# PCR-Badge-2015.net
KiCad netlist of a schematic drawn in EAGLE
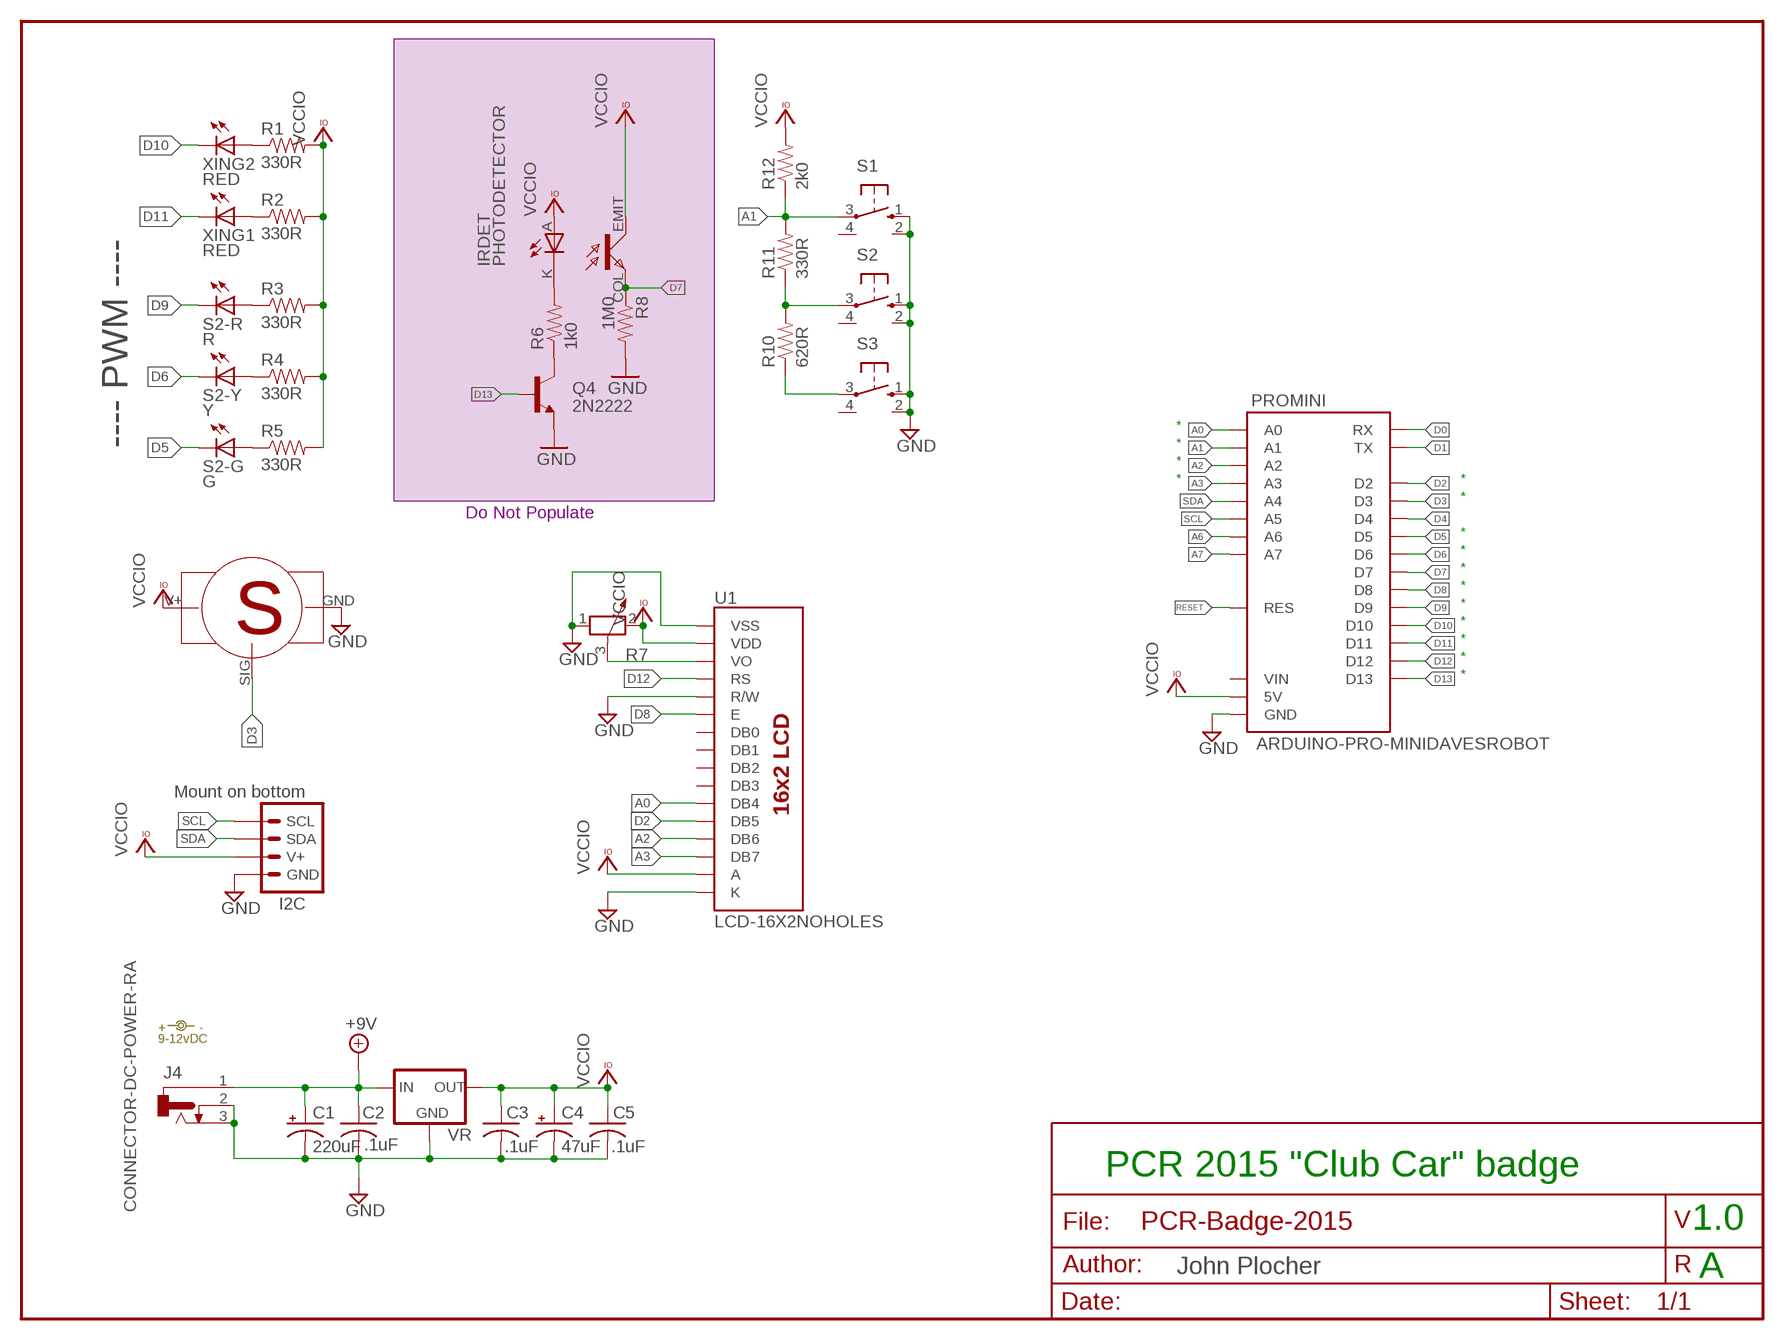
[diagram p0: schematic, sheet 1]

(export (version "E")
  (design (tool "Eeschema 10.0.6"))
  (components
    (comp (ref "C1")
      (value "220uF")
      (footprint "eagle-import:E5-10.5")
      (libsource (lib "eagle-import") (part "CAP-POLPTH-5MM"))
    )
    (comp (ref "C2")
      (value ".1uF")
      (footprint "eagle-import:C050-024X044")
      (libsource (lib "eagle-import") (part "CAP"))
    )
    (comp (ref "C3")
      (value ".1uF")
      (footprint "eagle-import:C050-024X044")
      (libsource (lib "eagle-import") (part "CAP"))
    )
    (comp (ref "C4")
      (value "47uF")
      (footprint "eagle-import:E5-10.5")
      (libsource (lib "eagle-import") (part "CAP-POLPTH-5MM"))
    )
    (comp (ref "C5")
      (value ".1uF")
      (footprint "eagle-import:C050-024X044")
      (libsource (lib "eagle-import") (part "CAP"))
    )
    (comp (ref "I2C")
      (value "Mount on bottom")
      (footprint "eagle-import:I2C")
      (libsource (lib "eagle-import") (part "CONNECTOR-I2C"))
    )
    (comp (ref "IRDET")
      (value "PHOTODETECTOR")
      (footprint "eagle-import:RPR220")
      (libsource (lib "eagle-import") (part "PHOTODETECTOR"))
    )
    (comp (ref "J4")
      (value "CONNECTOR-DC-POWER-RA")
      (footprint "eagle-import:DCJ0202")
      (libsource (lib "eagle-import") (part "CONNECTOR-DC-POWER-RA"))
    )
    (comp (ref "POWER")
      (value "9-12vDC")
      (footprint "eagle-import:POWER_USAGE")
      (libsource (lib "eagle-import") (part "DOC-POWER_LABEL"))
    )
    (comp (ref "PROMINI")
      (value "ARDUINO-PRO-MINIDAVESROBOT")
      (footprint "eagle-import:ARDUINO_PRO_MINI_DAVEK")
      (libsource (lib "eagle-import") (part "ARDUINO-PRO-MINIDAVESROBOT"))
    )
    (comp (ref "Q4")
      (value "2N2222")
      (footprint "eagle-import:TO-92")
      (libsource (lib "eagle-import") (part "NPN-TO92"))
    )
    (comp (ref "R1")
      (value "330R")
      (footprint "eagle-import:1_6W-RES")
      (libsource (lib "eagle-import") (part "RPTH-1/6W"))
    )
    (comp (ref "R2")
      (value "330R")
      (footprint "eagle-import:1_6W-RES")
      (libsource (lib "eagle-import") (part "RPTH-1/6W"))
    )
    (comp (ref "R3")
      (value "330R")
      (footprint "eagle-import:1_6W-RES")
      (libsource (lib "eagle-import") (part "RPTH-1/6W"))
    )
    (comp (ref "R4")
      (value "330R")
      (footprint "eagle-import:1_6W-RES")
      (libsource (lib "eagle-import") (part "RPTH-1/6W"))
    )
    (comp (ref "R5")
      (value "330R")
      (footprint "eagle-import:1_6W-RES")
      (libsource (lib "eagle-import") (part "RPTH-1/6W"))
    )
    (comp (ref "R6")
      (value "1k0")
      (footprint "eagle-import:1_6W-RES")
      (libsource (lib "eagle-import") (part "RPTH-1/6W"))
    )
    (comp (ref "R7")
      (value "R-POTENTIOMETERB25U")
      (footprint "eagle-import:B25U")
      (libsource (lib "eagle-import") (part "R-POTENTIOMETERB25U"))
    )
    (comp (ref "R8")
      (value "1M0")
      (footprint "eagle-import:1_6W-RES")
      (libsource (lib "eagle-import") (part "RPTH-1/6W"))
    )
    (comp (ref "R10")
      (value "620R")
      (footprint "eagle-import:1_6W-RES")
      (libsource (lib "eagle-import") (part "RPTH-1/6W"))
    )
    (comp (ref "R11")
      (value "330R")
      (footprint "eagle-import:1_6W-RES")
      (libsource (lib "eagle-import") (part "RPTH-1/6W"))
    )
    (comp (ref "R12")
      (value "2k0")
      (footprint "eagle-import:1_6W-RES")
      (libsource (lib "eagle-import") (part "RPTH-1/6W"))
    )
    (comp (ref "S1")
      (value "SWITCH-(ON)SMALLPADS")
      (footprint "eagle-import:4P-PTH-6.0X6.0X5.0H")
      (libsource (lib "eagle-import") (part "SWITCH-(ON)SMALLPADS"))
    )
    (comp (ref "S2")
      (value "SWITCH-(ON)SMALLPADS")
      (footprint "eagle-import:4P-PTH-6.0X6.0X5.0H")
      (libsource (lib "eagle-import") (part "SWITCH-(ON)SMALLPADS"))
    )
    (comp (ref "S2-G")
      (value "G")
      (footprint "eagle-import:LED5MM")
      (libsource (lib "eagle-import") (part "LEDLED5MM"))
    )
    (comp (ref "S2-R")
      (value "R")
      (footprint "eagle-import:LED5MM")
      (libsource (lib "eagle-import") (part "LEDLED5MM"))
    )
    (comp (ref "S2-Y")
      (value "Y")
      (footprint "eagle-import:LED5MM")
      (libsource (lib "eagle-import") (part "LEDLED5MM"))
    )
    (comp (ref "S3")
      (value "SWITCH-(ON)SMALLPADS")
      (footprint "eagle-import:4P-PTH-6.0X6.0X5.0H")
      (libsource (lib "eagle-import") (part "SWITCH-(ON)SMALLPADS"))
    )
    (comp (ref "SERVO")
      (value "SERVO")
      (footprint "eagle-import:SERVO")
      (libsource (lib "eagle-import") (part "SERVO"))
    )
    (comp (ref "SERVO1")
      (value "SERVO")
      (footprint "eagle-import:SERVO-9G")
      (libsource (lib "eagle-import") (part "SERVO-CUTOUT"))
    )
    (comp (ref "U1")
      (value "LCD-16X2NOHOLES")
      (footprint "eagle-import:LCD-16X2_NOHOLES")
      (libsource (lib "eagle-import") (part "LCD-16X2NOHOLES"))
    )
    (comp (ref "VR")
      (value "VREG_78XX-TO-220")
      (footprint "eagle-import:TO-220-ALT")
      (libsource (lib "eagle-import") (part "VREG_78XX-TO-220"))
    )
    (comp (ref "XING1")
      (value "RED")
      (footprint "eagle-import:LED5MM")
      (libsource (lib "eagle-import") (part "LEDLED5MM"))
    )
    (comp (ref "XING2")
      (value "RED")
      (footprint "eagle-import:LED5MM")
      (libsource (lib "eagle-import") (part "LEDLED5MM"))
    )
  )
  (nets
    (net (code "1") (name "+9V") (class "Default")
      (node (ref "C1") (pin "+") (pinfunction "+_+") (pintype "passive"))
      (node (ref "C2") (pin "1") (pinfunction "1_1") (pintype "passive"))
      (node (ref "J4") (pin "1") (pinfunction "1_1") (pintype "passive"))
      (node (ref "VR") (pin "IN") (pinfunction "IN_IN") (pintype "input"))
    )
    (net (code "2") (name "A0") (class "Default")
      (node (ref "PROMINI") (pin "AD0") (pinfunction "A0_AD0") (pintype "bidirectional"))
      (node (ref "U1") (pin "11") (pinfunction "DB4_11") (pintype "bidirectional"))
    )
    (net (code "3") (name "A1") (class "Default")
      (node (ref "PROMINI") (pin "AD1") (pinfunction "A1_AD1") (pintype "bidirectional"))
      (node (ref "R11") (pin "2") (pinfunction "2_2") (pintype "passive"))
      (node (ref "R12") (pin "1") (pinfunction "1_1") (pintype "passive"))
      (node (ref "S1") (pin "3") (pinfunction "P_3") (pintype "passive"))
    )
    (net (code "4") (name "A2") (class "Default")
      (node (ref "PROMINI") (pin "AD2") (pinfunction "A2_AD2") (pintype "bidirectional"))
      (node (ref "U1") (pin "13") (pinfunction "DB6_13") (pintype "bidirectional"))
    )
    (net (code "5") (name "A3") (class "Default")
      (node (ref "PROMINI") (pin "AD3") (pinfunction "A3_AD3") (pintype "bidirectional"))
      (node (ref "U1") (pin "14") (pinfunction "DB7_14") (pintype "bidirectional"))
    )
    (net (code "6") (name "A6") (class "Default")
      (node (ref "PROMINI") (pin "AD6") (pinfunction "A6_AD6") (pintype "bidirectional"))
    )
    (net (code "7") (name "A7") (class "Default")
      (node (ref "PROMINI") (pin "AD7") (pinfunction "A7_AD7") (pintype "bidirectional"))
    )
    (net (code "8") (name "D0") (class "Default")
      (node (ref "PROMINI") (pin "RX") (pinfunction "RX_RX") (pintype "bidirectional"))
    )
    (net (code "9") (name "D1") (class "Default")
      (node (ref "PROMINI") (pin "TX@1") (pinfunction "TX_TX@1") (pintype "bidirectional"))
    )
    (net (code "10") (name "D2") (class "Default")
      (node (ref "PROMINI") (pin "D2") (pinfunction "D2_D2") (pintype "bidirectional"))
      (node (ref "U1") (pin "12") (pinfunction "DB5_12") (pintype "bidirectional"))
    )
    (net (code "11") (name "D3") (class "Default")
      (node (ref "PROMINI") (pin "D3") (pinfunction "D3_D3") (pintype "bidirectional"))
      (node (ref "SERVO") (pin "SIG") (pinfunction "PWM_SIG") (pintype "input"))
    )
    (net (code "12") (name "D4") (class "Default")
      (node (ref "PROMINI") (pin "D4") (pinfunction "D4_D4") (pintype "bidirectional"))
    )
    (net (code "13") (name "D5") (class "Default")
      (node (ref "PROMINI") (pin "D5") (pinfunction "D5_D5") (pintype "bidirectional"))
      (node (ref "S2-G") (pin "K") (pinfunction "C_K") (pintype "passive"))
    )
    (net (code "14") (name "D6") (class "Default")
      (node (ref "PROMINI") (pin "D6") (pinfunction "D6_D6") (pintype "bidirectional"))
      (node (ref "S2-Y") (pin "K") (pinfunction "C_K") (pintype "passive"))
    )
    (net (code "15") (name "D7") (class "Default")
      (node (ref "IRDET") (pin "COL") (pinfunction "COL_COL") (pintype "passive"))
      (node (ref "PROMINI") (pin "D7") (pinfunction "D7_D7") (pintype "bidirectional"))
      (node (ref "R8") (pin "1") (pinfunction "1_1") (pintype "passive"))
    )
    (net (code "16") (name "D8") (class "Default")
      (node (ref "PROMINI") (pin "D8") (pinfunction "D8_D8") (pintype "bidirectional"))
      (node (ref "U1") (pin "6") (pinfunction "E_6") (pintype "input"))
    )
    (net (code "17") (name "D9") (class "Default")
      (node (ref "PROMINI") (pin "D9") (pinfunction "D9_D9") (pintype "bidirectional"))
      (node (ref "S2-R") (pin "K") (pinfunction "C_K") (pintype "passive"))
    )
    (net (code "18") (name "D10") (class "Default")
      (node (ref "PROMINI") (pin "D10") (pinfunction "D10_D10") (pintype "bidirectional"))
      (node (ref "XING2") (pin "K") (pinfunction "C_K") (pintype "passive"))
    )
    (net (code "19") (name "D11") (class "Default")
      (node (ref "PROMINI") (pin "D11") (pinfunction "D11_D11") (pintype "bidirectional"))
      (node (ref "XING1") (pin "K") (pinfunction "C_K") (pintype "passive"))
    )
    (net (code "20") (name "D12") (class "Default")
      (node (ref "PROMINI") (pin "D12") (pinfunction "D12_D12") (pintype "bidirectional"))
      (node (ref "U1") (pin "4") (pinfunction "RS_4") (pintype "input"))
    )
    (net (code "21") (name "D13") (class "Default")
      (node (ref "PROMINI") (pin "D13") (pinfunction "D13_D13") (pintype "bidirectional"))
      (node (ref "Q4") (pin "2") (pinfunction "B_2") (pintype "passive"))
    )
    (net (code "22") (name "GND") (class "Default")
      (node (ref "C1") (pin "-") (pinfunction "-_-") (pintype "passive"))
      (node (ref "C2") (pin "2") (pinfunction "2_2") (pintype "passive"))
      (node (ref "C3") (pin "2") (pinfunction "2_2") (pintype "passive"))
      (node (ref "C4") (pin "-") (pinfunction "-_-") (pintype "passive"))
      (node (ref "C5") (pin "2") (pinfunction "2_2") (pintype "passive"))
      (node (ref "I2C") (pin "GND") (pinfunction "GND_GND") (pintype "passive"))
      (node (ref "J4") (pin "2") (pinfunction "2_2") (pintype "passive"))
      (node (ref "J4") (pin "3") (pinfunction "3_3") (pintype "passive"))
      (node (ref "PROMINI") (pin "GND@1") (pinfunction "GND_GND@1") (pintype "bidirectional"))
      (node (ref "PROMINI") (pin "GND@2") (pinfunction "GND_GND@2") (pintype "bidirectional"))
      (node (ref "PROMINI") (pin "GND@4") (pinfunction "GND_GND@4") (pintype "bidirectional"))
      (node (ref "Q4") (pin "1") (pinfunction "E_1") (pintype "passive"))
      (node (ref "R7") (pin "1") (pinfunction "1_1") (pintype "passive"))
      (node (ref "R8") (pin "2") (pinfunction "2_2") (pintype "passive"))
      (node (ref "S1") (pin "1") (pinfunction "S_1") (pintype "passive"))
      (node (ref "S1") (pin "2") (pinfunction "S1_2") (pintype "passive"))
      (node (ref "S2") (pin "1") (pinfunction "S_1") (pintype "passive"))
      (node (ref "S2") (pin "2") (pinfunction "S1_2") (pintype "passive"))
      (node (ref "S3") (pin "1") (pinfunction "S_1") (pintype "passive"))
      (node (ref "S3") (pin "2") (pinfunction "S1_2") (pintype "passive"))
      (node (ref "SERVO") (pin "GND") (pinfunction "GND_GND") (pintype "power_in"))
      (node (ref "U1") (pin "1") (pinfunction "VSS_1") (pintype "power_in"))
      (node (ref "U1") (pin "16") (pinfunction "K_16") (pintype "power_in"))
      (node (ref "U1") (pin "5") (pinfunction "R/W_5") (pintype "input"))
      (node (ref "VR") (pin "GND") (pinfunction "GND_GND") (pintype "input"))
    )
    (net (code "23") (name "Net-(IRDET-PadK)") (class "Default")
      (node (ref "IRDET") (pin "K") (pinfunction "K_K") (pintype "passive"))
      (node (ref "R6") (pin "2") (pinfunction "2_2") (pintype "passive"))
    )
    (net (code "24") (name "Net-(Q4-C)") (class "Default")
      (node (ref "Q4") (pin "3") (pinfunction "C_3") (pintype "passive"))
      (node (ref "R6") (pin "1") (pinfunction "1_1") (pintype "passive"))
    )
    (net (code "25") (name "Net-(R1-Pad1)") (class "Default")
      (node (ref "R1") (pin "1") (pinfunction "1_1") (pintype "passive"))
      (node (ref "XING2") (pin "A") (pinfunction "A_A") (pintype "passive"))
    )
    (net (code "26") (name "Net-(R2-Pad1)") (class "Default")
      (node (ref "R2") (pin "1") (pinfunction "1_1") (pintype "passive"))
      (node (ref "XING1") (pin "A") (pinfunction "A_A") (pintype "passive"))
    )
    (net (code "27") (name "Net-(R3-Pad1)") (class "Default")
      (node (ref "R3") (pin "1") (pinfunction "1_1") (pintype "passive"))
      (node (ref "S2-R") (pin "A") (pinfunction "A_A") (pintype "passive"))
    )
    (net (code "28") (name "Net-(R4-Pad1)") (class "Default")
      (node (ref "R4") (pin "1") (pinfunction "1_1") (pintype "passive"))
      (node (ref "S2-Y") (pin "A") (pinfunction "A_A") (pintype "passive"))
    )
    (net (code "29") (name "Net-(R5-Pad1)") (class "Default")
      (node (ref "R5") (pin "1") (pinfunction "1_1") (pintype "passive"))
      (node (ref "S2-G") (pin "A") (pinfunction "A_A") (pintype "passive"))
    )
    (net (code "30") (name "Net-(S2-P)") (class "Default")
      (node (ref "R10") (pin "2") (pinfunction "2_2") (pintype "passive"))
      (node (ref "R11") (pin "1") (pinfunction "1_1") (pintype "passive"))
      (node (ref "S2") (pin "3") (pinfunction "P_3") (pintype "passive"))
    )
    (net (code "31") (name "Net-(S3-P)") (class "Default")
      (node (ref "R10") (pin "1") (pinfunction "1_1") (pintype "passive"))
      (node (ref "S3") (pin "3") (pinfunction "P_3") (pintype "passive"))
    )
    (net (code "32") (name "Net-(U1-VO)") (class "Default")
      (node (ref "R7") (pin "3") (pinfunction "3_3") (pintype "passive"))
      (node (ref "U1") (pin "3") (pinfunction "VO_3") (pintype "bidirectional"))
    )
    (net (code "33") (name "RESET") (class "Default")
      (node (ref "PROMINI") (pin "RES") (pinfunction "RES_RES") (pintype "bidirectional"))
      (node (ref "PROMINI") (pin "RES@1") (pinfunction "RES_RES@1") (pintype "bidirectional"))
    )
    (net (code "34") (name "SCL") (class "Default")
      (node (ref "I2C") (pin "SCL") (pinfunction "SCL_SCL") (pintype "passive"))
      (node (ref "PROMINI") (pin "AD5") (pinfunction "A5_AD5") (pintype "bidirectional"))
    )
    (net (code "35") (name "SDA") (class "Default")
      (node (ref "I2C") (pin "SDA") (pinfunction "SDA_SDA") (pintype "passive"))
      (node (ref "PROMINI") (pin "AD4") (pinfunction "A4_AD4") (pintype "bidirectional"))
    )
    (net (code "36") (name "VCCIO") (class "Default")
      (node (ref "C3") (pin "1") (pinfunction "1_1") (pintype "passive"))
      (node (ref "C4") (pin "+") (pinfunction "+_+") (pintype "passive"))
      (node (ref "C5") (pin "1") (pinfunction "1_1") (pintype "passive"))
      (node (ref "I2C") (pin "V+") (pinfunction "V+_V+") (pintype "passive"))
      (node (ref "IRDET") (pin "A") (pinfunction "A_A") (pintype "passive"))
      (node (ref "IRDET") (pin "EMIT") (pinfunction "EMIT_EMIT") (pintype "passive"))
      (node (ref "PROMINI") (pin "5V") (pinfunction "5V_5V") (pintype "bidirectional"))
      (node (ref "R1") (pin "2") (pinfunction "2_2") (pintype "passive"))
      (node (ref "R12") (pin "2") (pinfunction "2_2") (pintype "passive"))
      (node (ref "R2") (pin "2") (pinfunction "2_2") (pintype "passive"))
      (node (ref "R3") (pin "2") (pinfunction "2_2") (pintype "passive"))
      (node (ref "R4") (pin "2") (pinfunction "2_2") (pintype "passive"))
      (node (ref "R5") (pin "2") (pinfunction "2_2") (pintype "passive"))
      (node (ref "R7") (pin "2") (pinfunction "2_2") (pintype "passive"))
      (node (ref "SERVO") (pin "V+") (pinfunction "V+_V+") (pintype "power_in"))
      (node (ref "U1") (pin "15") (pinfunction "A_15") (pintype "power_in"))
      (node (ref "U1") (pin "2") (pinfunction "VDD_2") (pintype "power_in"))
      (node (ref "VR") (pin "OUT") (pinfunction "OUT_OUT") (pintype "output"))
    )
    (net (code "37") (name "unconnected-(PROMINI-PadVIN)") (class "Default")
      (node (ref "PROMINI") (pin "VIN") (pinfunction "VIN_VIN") (pintype "bidirectional"))
    )
    (net (code "38") (name "unconnected-(S1-P1-Pad4)") (class "Default")
      (node (ref "S1") (pin "4") (pinfunction "P1_4") (pintype "passive"))
    )
    (net (code "39") (name "unconnected-(S2-P1-Pad4)") (class "Default")
      (node (ref "S2") (pin "4") (pinfunction "P1_4") (pintype "passive"))
    )
    (net (code "40") (name "unconnected-(S3-P1-Pad4)") (class "Default")
      (node (ref "S3") (pin "4") (pinfunction "P1_4") (pintype "passive"))
    )
    (net (code "41") (name "unconnected-(U1-DB0-Pad7)") (class "Default")
      (node (ref "U1") (pin "7") (pinfunction "DB0_7") (pintype "bidirectional"))
    )
    (net (code "42") (name "unconnected-(U1-DB1-Pad8)") (class "Default")
      (node (ref "U1") (pin "8") (pinfunction "DB1_8") (pintype "bidirectional"))
    )
    (net (code "43") (name "unconnected-(U1-DB2-Pad9)") (class "Default")
      (node (ref "U1") (pin "9") (pinfunction "DB2_9") (pintype "bidirectional"))
    )
    (net (code "44") (name "unconnected-(U1-DB3-Pad10)") (class "Default")
      (node (ref "U1") (pin "10") (pinfunction "DB3_10") (pintype "bidirectional"))
    )
  )
)
